# dimmer.net
KiCad netlist of a schematic drawn in EAGLE
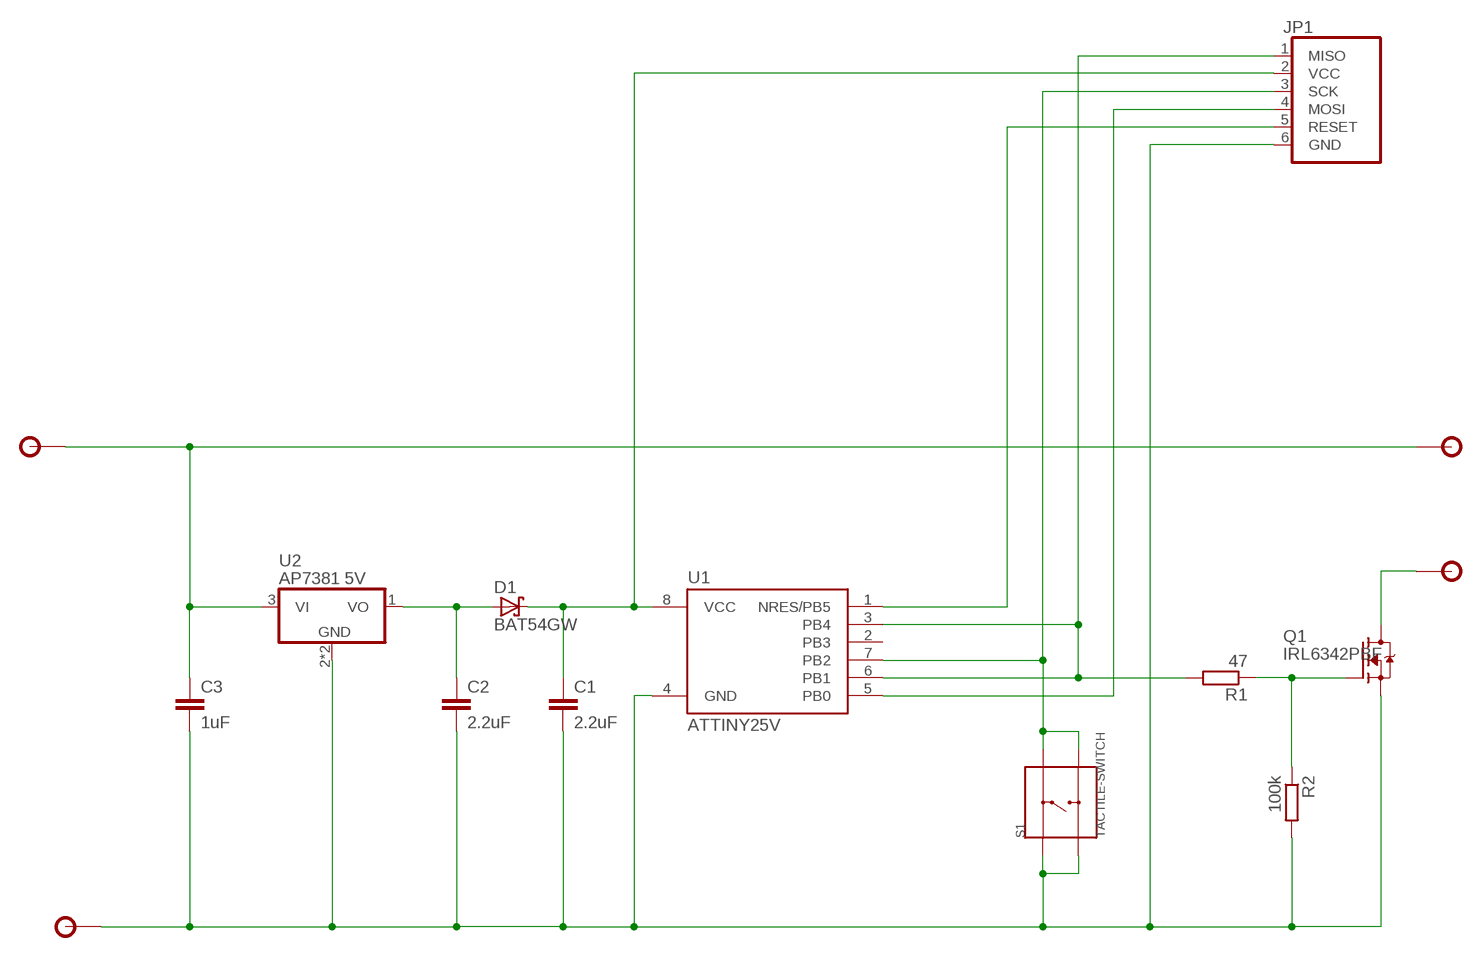
[diagram p0: schematic, sheet 1]

(export (version "E")
  (design (tool "Eeschema 10.0.6"))
  (components
    (comp (ref "C1")
      (value "2.2uF")
      (footprint "eagle-import:C0805")
      (libsource (lib "eagle-import") (part "C-EUC0805"))
    )
    (comp (ref "C2")
      (value "2.2uF")
      (footprint "eagle-import:C0805")
      (libsource (lib "eagle-import") (part "C-EUC0805"))
    )
    (comp (ref "C3")
      (value "1uF")
      (footprint "eagle-import:C0805")
      (libsource (lib "eagle-import") (part "C-EUC0805"))
    )
    (comp (ref "D1")
      (value "BAT54GW")
      (footprint "eagle-import:SOD123FL")
      (libsource (lib "eagle-import") (part "SCHOTKY"))
    )
    (comp (ref "JP1")
      (value "AVR-ISP-6PIN")
      (footprint "eagle-import:2X03")
      (libsource (lib "eagle-import") (part "AVR-ISP-6PIN"))
    )
    (comp (ref "Q1")
      (value "IRL6342PBF")
      (footprint "eagle-import:SO-8")
      (libsource (lib "eagle-import") (part "IRL6342PBF"))
    )
    (comp (ref "R1")
      (value "47")
      (footprint "eagle-import:R0805")
      (libsource (lib "eagle-import") (part "R-EU_R0805"))
    )
    (comp (ref "R2")
      (value "100k")
      (footprint "eagle-import:R0805")
      (libsource (lib "eagle-import") (part "R-EU_R0805"))
    )
    (comp (ref "S1")
      (value "TACTILE-SWITCH")
      (footprint "eagle-import:SW4-SMD-4.5MM")
      (libsource (lib "eagle-import") (part "TACTILE-SWITCH"))
    )
    (comp (ref "U1")
      (value "ATTINY25V")
      (footprint "eagle-import:SOIC8_EIAJ_208MIL")
      (libsource (lib "eagle-import") (part "ATTINY25SV-10"))
    )
    (comp (ref "U2")
      (value "AP7381 5V")
      (footprint "eagle-import:SOT89")
      (libsource (lib "eagle-import") (part "AP7381"))
    )
    (comp (ref "X1")
      (value "PAD")
      (footprint "eagle-import:PAD-L")
      (libsource (lib "eagle-import") (part "PAD"))
    )
    (comp (ref "X2")
      (value "PAD")
      (footprint "eagle-import:PAD-L")
      (libsource (lib "eagle-import") (part "PAD"))
    )
    (comp (ref "X3")
      (value "PAD")
      (footprint "eagle-import:PAD-L")
      (libsource (lib "eagle-import") (part "PAD"))
    )
    (comp (ref "X4")
      (value "PAD")
      (footprint "eagle-import:PAD-L")
      (libsource (lib "eagle-import") (part "PAD"))
    )
  )
  (nets
    (net (code "1") (name "Net-(JP1-GND)") (class "Default")
      (node (ref "C1") (pin "2") (pinfunction "2_2") (pintype "passive"))
      (node (ref "C2") (pin "2") (pinfunction "2_2") (pintype "passive"))
      (node (ref "C3") (pin "2") (pinfunction "2_2") (pintype "passive"))
      (node (ref "JP1") (pin "6") (pinfunction "GND_6") (pintype "power_in"))
      (node (ref "Q1") (pin "1") (pinfunction "S_1") (pintype "passive"))
      (node (ref "Q1") (pin "2") (pinfunction "S_2") (pintype "passive"))
      (node (ref "Q1") (pin "3") (pinfunction "S_3") (pintype "passive"))
      (node (ref "R2") (pin "2") (pinfunction "2_2") (pintype "passive"))
      (node (ref "S1") (pin "P$1") (pinfunction "A0_P$1") (pintype "bidirectional"))
      (node (ref "S1") (pin "P$3") (pinfunction "B0_P$3") (pintype "bidirectional"))
      (node (ref "U1") (pin "4") (pinfunction "GND_4") (pintype "power_in"))
      (node (ref "U2") (pin "2") (pinfunction "GND_2") (pintype "passive"))
      (node (ref "U2") (pin "2@1") (pinfunction "GND_2@1") (pintype "passive"))
      (node (ref "X2") (pin "P$1") (pinfunction "P$1_P$1") (pintype "bidirectional"))
    )
    (net (code "2") (name "Net-(JP1-MISO)") (class "Default")
      (node (ref "JP1") (pin "1") (pinfunction "MISO_1") (pintype "bidirectional"))
      (node (ref "R1") (pin "2") (pinfunction "2_2") (pintype "passive"))
      (node (ref "U1") (pin "3") (pinfunction "PB4_3") (pintype "bidirectional"))
      (node (ref "U1") (pin "6") (pinfunction "PB1_6") (pintype "bidirectional"))
    )
    (net (code "3") (name "Net-(JP1-MOSI)") (class "Default")
      (node (ref "JP1") (pin "4") (pinfunction "MOSI_4") (pintype "bidirectional"))
      (node (ref "U1") (pin "5") (pinfunction "PB0_5") (pintype "bidirectional"))
    )
    (net (code "4") (name "Net-(JP1-RESET)") (class "Default")
      (node (ref "JP1") (pin "5") (pinfunction "RESET_5") (pintype "bidirectional"))
      (node (ref "U1") (pin "1") (pinfunction "NRES/PB5_1") (pintype "bidirectional"))
    )
    (net (code "5") (name "Net-(JP1-SCK)") (class "Default")
      (node (ref "JP1") (pin "3") (pinfunction "SCK_3") (pintype "bidirectional"))
      (node (ref "S1") (pin "P$2") (pinfunction "A1_P$2") (pintype "bidirectional"))
      (node (ref "S1") (pin "P$4") (pinfunction "B1_P$4") (pintype "bidirectional"))
      (node (ref "U1") (pin "7") (pinfunction "PB2_7") (pintype "bidirectional"))
    )
    (net (code "6") (name "Net-(JP1-VCC)") (class "Default")
      (node (ref "C1") (pin "1") (pinfunction "1_1") (pintype "passive"))
      (node (ref "D1") (pin "C") (pinfunction "C_C") (pintype "passive"))
      (node (ref "JP1") (pin "2") (pinfunction "VCC_2") (pintype "power_in"))
      (node (ref "U1") (pin "8") (pinfunction "VCC_8") (pintype "power_in"))
    )
    (net (code "7") (name "Net-(Q1-D-Pad5)") (class "Default")
      (node (ref "Q1") (pin "5") (pinfunction "D_5") (pintype "passive"))
      (node (ref "Q1") (pin "6") (pinfunction "D_6") (pintype "passive"))
      (node (ref "Q1") (pin "7") (pinfunction "D_7") (pintype "passive"))
      (node (ref "Q1") (pin "8") (pinfunction "D_8") (pintype "passive"))
      (node (ref "X4") (pin "P$1") (pinfunction "P$1_P$1") (pintype "bidirectional"))
    )
    (net (code "8") (name "Net-(Q1-G)") (class "Default")
      (node (ref "Q1") (pin "4") (pinfunction "G_4") (pintype "passive"))
      (node (ref "R1") (pin "1") (pinfunction "1_1") (pintype "passive"))
      (node (ref "R2") (pin "1") (pinfunction "1_1") (pintype "passive"))
    )
    (net (code "9") (name "Net-(U2-VI)") (class "Default")
      (node (ref "C3") (pin "1") (pinfunction "1_1") (pintype "passive"))
      (node (ref "U2") (pin "3") (pinfunction "VI_3") (pintype "input"))
      (node (ref "X1") (pin "P$1") (pinfunction "P$1_P$1") (pintype "bidirectional"))
      (node (ref "X3") (pin "P$1") (pinfunction "P$1_P$1") (pintype "bidirectional"))
    )
    (net (code "10") (name "Net-(U2-VO)") (class "Default")
      (node (ref "C2") (pin "1") (pinfunction "1_1") (pintype "passive"))
      (node (ref "D1") (pin "A") (pinfunction "A_A") (pintype "passive"))
      (node (ref "U2") (pin "1") (pinfunction "VO_1") (pintype "passive"))
    )
    (net (code "11") (name "unconnected-(U1-PB3-Pad2)") (class "Default")
      (node (ref "U1") (pin "2") (pinfunction "PB3_2") (pintype "bidirectional"))
    )
  )
)
